# Fishbot_receiver.net
KiCad netlist of a schematic drawn in EAGLE
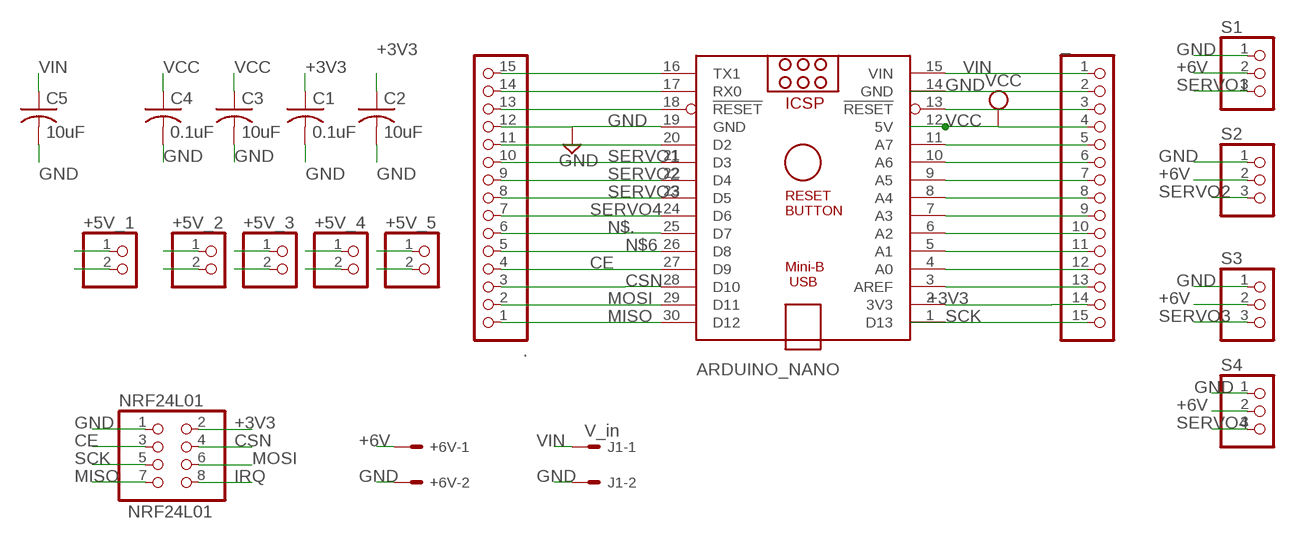
[diagram p0: schematic, sheet 1]

(export (version "E")
  (design (tool "Eeschema 10.0.6"))
  (components
    (comp (ref "+5V_1")
      (value "PINHD-1X2")
      (footprint "eagle-import:1X02")
      (libsource (lib "eagle-import") (part "PINHD-1X2"))
    )
    (comp (ref "+5V_2")
      (value "PINHD-1X2")
      (footprint "eagle-import:1X02")
      (libsource (lib "eagle-import") (part "PINHD-1X2"))
    )
    (comp (ref "+5V_3")
      (value "PINHD-1X2")
      (footprint "eagle-import:1X02")
      (libsource (lib "eagle-import") (part "PINHD-1X2"))
    )
    (comp (ref "+5V_4")
      (value "PINHD-1X2")
      (footprint "eagle-import:1X02")
      (libsource (lib "eagle-import") (part "PINHD-1X2"))
    )
    (comp (ref "+5V_5")
      (value "PINHD-1X2")
      (footprint "eagle-import:1X02")
      (libsource (lib "eagle-import") (part "PINHD-1X2"))
    )
    (comp (ref "+6V")
      (value "22-27-2021-02")
      (footprint "eagle-import:6410-02")
      (fields (field (name "MF") "MOLEX"))
      (libsource (lib "eagle-import") (part "22-?-0227-2021"))
    )
    (comp (ref ".")
      (value "PINHD-1X15")
      (footprint "eagle-import:1X15")
      (libsource (lib "eagle-import") (part "PINHD-1X15"))
    )
    (comp (ref "ARDUINO_NANO")
      (value "ARDUINO_NANO")
      (footprint "eagle-import:ARDUINO_NANO")
      (libsource (lib "eagle-import") (part "ARDUINO_NANO"))
    )
    (comp (ref "C1")
      (value "0.1uF")
      (footprint "eagle-import:C1206")
      (libsource (lib "eagle-import") (part "C-USC1206"))
    )
    (comp (ref "C2")
      (value "10uF")
      (footprint "eagle-import:C1206")
      (libsource (lib "eagle-import") (part "C-USC1206"))
    )
    (comp (ref "C3")
      (value "10uF")
      (footprint "eagle-import:C1206")
      (libsource (lib "eagle-import") (part "C-USC1206"))
    )
    (comp (ref "C4")
      (value "0.1uF")
      (footprint "eagle-import:C1206")
      (libsource (lib "eagle-import") (part "C-USC1206"))
    )
    (comp (ref "C5")
      (value "10uF")
      (footprint "eagle-import:C1206")
      (libsource (lib "eagle-import") (part "C-USC1206"))
    )
    (comp (ref "J1")
      (value "V_in")
      (footprint "eagle-import:6410-02")
      (fields (field (name "MF") "MOLEX"))
      (libsource (lib "eagle-import") (part "22-?-0227-2021"))
    )
    (comp (ref "NRF24L01")
      (value "PINHD-2X4")
      (footprint "eagle-import:2X04")
      (libsource (lib "eagle-import") (part "PINHD-2X4"))
    )
    (comp (ref "S1")
      (value "PINHD-1X3")
      (footprint "eagle-import:1X03")
      (libsource (lib "eagle-import") (part "PINHD-1X3"))
    )
    (comp (ref "S2")
      (value "PINHD-1X3")
      (footprint "eagle-import:1X03")
      (libsource (lib "eagle-import") (part "PINHD-1X3"))
    )
    (comp (ref "S3")
      (value "PINHD-1X3")
      (footprint "eagle-import:1X03")
      (libsource (lib "eagle-import") (part "PINHD-1X3"))
    )
    (comp (ref "S4")
      (value "PINHD-1X3")
      (footprint "eagle-import:1X03")
      (libsource (lib "eagle-import") (part "PINHD-1X3"))
    )
    (comp (ref "_")
      (value "PINHD-1X15")
      (footprint "eagle-import:1X15")
      (libsource (lib "eagle-import") (part "PINHD-1X15"))
    )
  )
  (nets
    (net (code "1") (name "/+3V3") (class "Default")
      (node (ref "ARDUINO_NANO") (pin "2") (pinfunction "3V3_2") (pintype "output"))
      (node (ref "C1") (pin "1") (pinfunction "1_1") (pintype "passive"))
      (node (ref "C2") (pin "1") (pinfunction "1_1") (pintype "passive"))
      (node (ref "NRF24L01") (pin "2") (pinfunction "2_2") (pintype "passive"))
      (node (ref "_") (pin "14") (pinfunction "14_14") (pintype "passive"))
    )
    (net (code "2") (name "/+6V") (class "Default")
      (node (ref "+6V") (pin "1") (pinfunction "S_1") (pintype "passive"))
      (node (ref "S1") (pin "2") (pinfunction "2_2") (pintype "passive"))
      (node (ref "S2") (pin "2") (pinfunction "2_2") (pintype "passive"))
      (node (ref "S3") (pin "2") (pinfunction "2_2") (pintype "passive"))
      (node (ref "S4") (pin "2") (pinfunction "2_2") (pintype "passive"))
    )
    (net (code "3") (name "/CE") (class "Default")
      (node (ref ".") (pin "4") (pinfunction "4_4") (pintype "passive"))
      (node (ref "ARDUINO_NANO") (pin "27") (pinfunction "D9_27") (pintype "bidirectional"))
      (node (ref "NRF24L01") (pin "3") (pinfunction "3_3") (pintype "passive"))
    )
    (net (code "4") (name "/CSN") (class "Default")
      (node (ref ".") (pin "3") (pinfunction "3_3") (pintype "passive"))
      (node (ref "ARDUINO_NANO") (pin "28") (pinfunction "D10_28") (pintype "bidirectional"))
      (node (ref "NRF24L01") (pin "4") (pinfunction "4_4") (pintype "passive"))
    )
    (net (code "5") (name "/IRQ") (class "Default")
      (node (ref "NRF24L01") (pin "8") (pinfunction "8_8") (pintype "passive"))
    )
    (net (code "6") (name "/MISO") (class "Default")
      (node (ref ".") (pin "1") (pinfunction "1_1") (pintype "passive"))
      (node (ref "ARDUINO_NANO") (pin "30") (pinfunction "D12_30") (pintype "bidirectional"))
      (node (ref "NRF24L01") (pin "7") (pinfunction "7_7") (pintype "passive"))
    )
    (net (code "7") (name "/MOSI") (class "Default")
      (node (ref ".") (pin "2") (pinfunction "2_2") (pintype "passive"))
      (node (ref "ARDUINO_NANO") (pin "29") (pinfunction "D11_29") (pintype "bidirectional"))
      (node (ref "NRF24L01") (pin "6") (pinfunction "6_6") (pintype "passive"))
    )
    (net (code "8") (name "/N$.") (class "Default")
      (node (ref ".") (pin "6") (pinfunction "6_6") (pintype "passive"))
      (node (ref "ARDUINO_NANO") (pin "25") (pinfunction "D7_25") (pintype "bidirectional"))
    )
    (net (code "9") (name "/N$6") (class "Default")
      (node (ref ".") (pin "5") (pinfunction "5_5") (pintype "passive"))
      (node (ref "ARDUINO_NANO") (pin "26") (pinfunction "D8_26") (pintype "bidirectional"))
    )
    (net (code "10") (name "/SCK") (class "Default")
      (node (ref "ARDUINO_NANO") (pin "1") (pinfunction "D13_1") (pintype "bidirectional"))
      (node (ref "NRF24L01") (pin "5") (pinfunction "5_5") (pintype "passive"))
      (node (ref "_") (pin "15") (pinfunction "15_15") (pintype "passive"))
    )
    (net (code "11") (name "/SERVO1") (class "Default")
      (node (ref ".") (pin "10") (pinfunction "10_10") (pintype "passive"))
      (node (ref "ARDUINO_NANO") (pin "21") (pinfunction "D3_21") (pintype "bidirectional"))
      (node (ref "S1") (pin "3") (pinfunction "3_3") (pintype "passive"))
    )
    (net (code "12") (name "/SERVO2") (class "Default")
      (node (ref ".") (pin "9") (pinfunction "9_9") (pintype "passive"))
      (node (ref "ARDUINO_NANO") (pin "22") (pinfunction "D4_22") (pintype "bidirectional"))
      (node (ref "S2") (pin "3") (pinfunction "3_3") (pintype "passive"))
    )
    (net (code "13") (name "/SERVO3") (class "Default")
      (node (ref ".") (pin "8") (pinfunction "8_8") (pintype "passive"))
      (node (ref "ARDUINO_NANO") (pin "23") (pinfunction "D5_23") (pintype "bidirectional"))
      (node (ref "S3") (pin "3") (pinfunction "3_3") (pintype "passive"))
    )
    (net (code "14") (name "/SERVO4") (class "Default")
      (node (ref ".") (pin "7") (pinfunction "7_7") (pintype "passive"))
      (node (ref "ARDUINO_NANO") (pin "24") (pinfunction "D6_24") (pintype "bidirectional"))
      (node (ref "S4") (pin "3") (pinfunction "3_3") (pintype "passive"))
    )
    (net (code "15") (name "/VIN") (class "Default")
      (node (ref "ARDUINO_NANO") (pin "15") (pinfunction "VIN_15") (pintype "power_in"))
      (node (ref "C5") (pin "1") (pinfunction "1_1") (pintype "passive"))
      (node (ref "J1") (pin "1") (pinfunction "S_1") (pintype "passive"))
      (node (ref "_") (pin "1") (pinfunction "1_1") (pintype "passive"))
    )
    (net (code "16") (name "GND") (class "Default")
      (node (ref "+5V_1") (pin "2") (pinfunction "2_2") (pintype "passive"))
      (node (ref "+5V_2") (pin "2") (pinfunction "2_2") (pintype "passive"))
      (node (ref "+5V_3") (pin "2") (pinfunction "2_2") (pintype "passive"))
      (node (ref "+5V_4") (pin "2") (pinfunction "2_2") (pintype "passive"))
      (node (ref "+5V_5") (pin "2") (pinfunction "2_2") (pintype "passive"))
      (node (ref "+6V") (pin "2") (pinfunction "S_2") (pintype "passive"))
      (node (ref ".") (pin "12") (pinfunction "12_12") (pintype "passive"))
      (node (ref "ARDUINO_NANO") (pin "14") (pinfunction "GND_14") (pintype "power_in"))
      (node (ref "ARDUINO_NANO") (pin "19") (pinfunction "GND_19") (pintype "power_in"))
      (node (ref "C1") (pin "2") (pinfunction "2_2") (pintype "passive"))
      (node (ref "C2") (pin "2") (pinfunction "2_2") (pintype "passive"))
      (node (ref "C3") (pin "2") (pinfunction "2_2") (pintype "passive"))
      (node (ref "C4") (pin "2") (pinfunction "2_2") (pintype "passive"))
      (node (ref "C5") (pin "2") (pinfunction "2_2") (pintype "passive"))
      (node (ref "J1") (pin "2") (pinfunction "S_2") (pintype "passive"))
      (node (ref "NRF24L01") (pin "1") (pinfunction "1_1") (pintype "passive"))
      (node (ref "S1") (pin "1") (pinfunction "1_1") (pintype "passive"))
      (node (ref "S2") (pin "1") (pinfunction "1_1") (pintype "passive"))
      (node (ref "S3") (pin "1") (pinfunction "1_1") (pintype "passive"))
      (node (ref "S4") (pin "1") (pinfunction "1_1") (pintype "passive"))
      (node (ref "_") (pin "2") (pinfunction "2_2") (pintype "passive"))
    )
    (net (code "17") (name "Net-(.-Pad13)") (class "Default")
      (node (ref ".") (pin "13") (pinfunction "13_13") (pintype "passive"))
      (node (ref "ARDUINO_NANO") (pin "18") (pinfunction "~{RESET}_18") (pintype "input"))
    )
    (net (code "18") (name "Net-(ARDUINO_NANO-A0)") (class "Default")
      (node (ref "ARDUINO_NANO") (pin "4") (pinfunction "A0_4") (pintype "bidirectional"))
      (node (ref "_") (pin "12") (pinfunction "12_12") (pintype "passive"))
    )
    (net (code "19") (name "Net-(ARDUINO_NANO-A1)") (class "Default")
      (node (ref "ARDUINO_NANO") (pin "5") (pinfunction "A1_5") (pintype "bidirectional"))
      (node (ref "_") (pin "11") (pinfunction "11_11") (pintype "passive"))
    )
    (net (code "20") (name "Net-(ARDUINO_NANO-A2)") (class "Default")
      (node (ref "ARDUINO_NANO") (pin "6") (pinfunction "A2_6") (pintype "bidirectional"))
      (node (ref "_") (pin "10") (pinfunction "10_10") (pintype "passive"))
    )
    (net (code "21") (name "Net-(ARDUINO_NANO-A3)") (class "Default")
      (node (ref "ARDUINO_NANO") (pin "7") (pinfunction "A3_7") (pintype "bidirectional"))
      (node (ref "_") (pin "9") (pinfunction "9_9") (pintype "passive"))
    )
    (net (code "22") (name "Net-(ARDUINO_NANO-A4)") (class "Default")
      (node (ref "ARDUINO_NANO") (pin "8") (pinfunction "A4_8") (pintype "bidirectional"))
      (node (ref "_") (pin "8") (pinfunction "8_8") (pintype "passive"))
    )
    (net (code "23") (name "Net-(ARDUINO_NANO-A5)") (class "Default")
      (node (ref "ARDUINO_NANO") (pin "9") (pinfunction "A5_9") (pintype "bidirectional"))
      (node (ref "_") (pin "7") (pinfunction "7_7") (pintype "passive"))
    )
    (net (code "24") (name "Net-(ARDUINO_NANO-A6)") (class "Default")
      (node (ref "ARDUINO_NANO") (pin "10") (pinfunction "A6_10") (pintype "bidirectional"))
      (node (ref "_") (pin "6") (pinfunction "6_6") (pintype "passive"))
    )
    (net (code "25") (name "Net-(ARDUINO_NANO-A7)") (class "Default")
      (node (ref "ARDUINO_NANO") (pin "11") (pinfunction "A7_11") (pintype "bidirectional"))
      (node (ref "_") (pin "5") (pinfunction "5_5") (pintype "passive"))
    )
    (net (code "26") (name "Net-(ARDUINO_NANO-AREF)") (class "Default")
      (node (ref "ARDUINO_NANO") (pin "3") (pinfunction "AREF_3") (pintype "input"))
      (node (ref "_") (pin "13") (pinfunction "13_13") (pintype "passive"))
    )
    (net (code "27") (name "Net-(ARDUINO_NANO-D2)") (class "Default")
      (node (ref ".") (pin "11") (pinfunction "11_11") (pintype "passive"))
      (node (ref "ARDUINO_NANO") (pin "20") (pinfunction "D2_20") (pintype "bidirectional"))
    )
    (net (code "28") (name "Net-(ARDUINO_NANO-RX0)") (class "Default")
      (node (ref ".") (pin "14") (pinfunction "14_14") (pintype "passive"))
      (node (ref "ARDUINO_NANO") (pin "17") (pinfunction "RX0_17") (pintype "bidirectional"))
    )
    (net (code "29") (name "Net-(ARDUINO_NANO-TX1)") (class "Default")
      (node (ref ".") (pin "15") (pinfunction "15_15") (pintype "passive"))
      (node (ref "ARDUINO_NANO") (pin "16") (pinfunction "TX1_16") (pintype "bidirectional"))
    )
    (net (code "30") (name "Net-(ARDUINO_NANO-~{RESET}-Pad13)") (class "Default")
      (node (ref "ARDUINO_NANO") (pin "13") (pinfunction "~{RESET}_13") (pintype "input"))
      (node (ref "_") (pin "3") (pinfunction "3_3") (pintype "passive"))
    )
    (net (code "31") (name "VCC") (class "Default")
      (node (ref "+5V_1") (pin "1") (pinfunction "1_1") (pintype "passive"))
      (node (ref "+5V_2") (pin "1") (pinfunction "1_1") (pintype "passive"))
      (node (ref "+5V_3") (pin "1") (pinfunction "1_1") (pintype "passive"))
      (node (ref "+5V_4") (pin "1") (pinfunction "1_1") (pintype "passive"))
      (node (ref "+5V_5") (pin "1") (pinfunction "1_1") (pintype "passive"))
      (node (ref "ARDUINO_NANO") (pin "12") (pinfunction "5V_12") (pintype "power_in"))
      (node (ref "C3") (pin "1") (pinfunction "1_1") (pintype "passive"))
      (node (ref "C4") (pin "1") (pinfunction "1_1") (pintype "passive"))
      (node (ref "_") (pin "4") (pinfunction "4_4") (pintype "passive"))
    )
  )
)
